# SCH_Two.net
KiCad netlist of a schematic drawn in Altium Designer
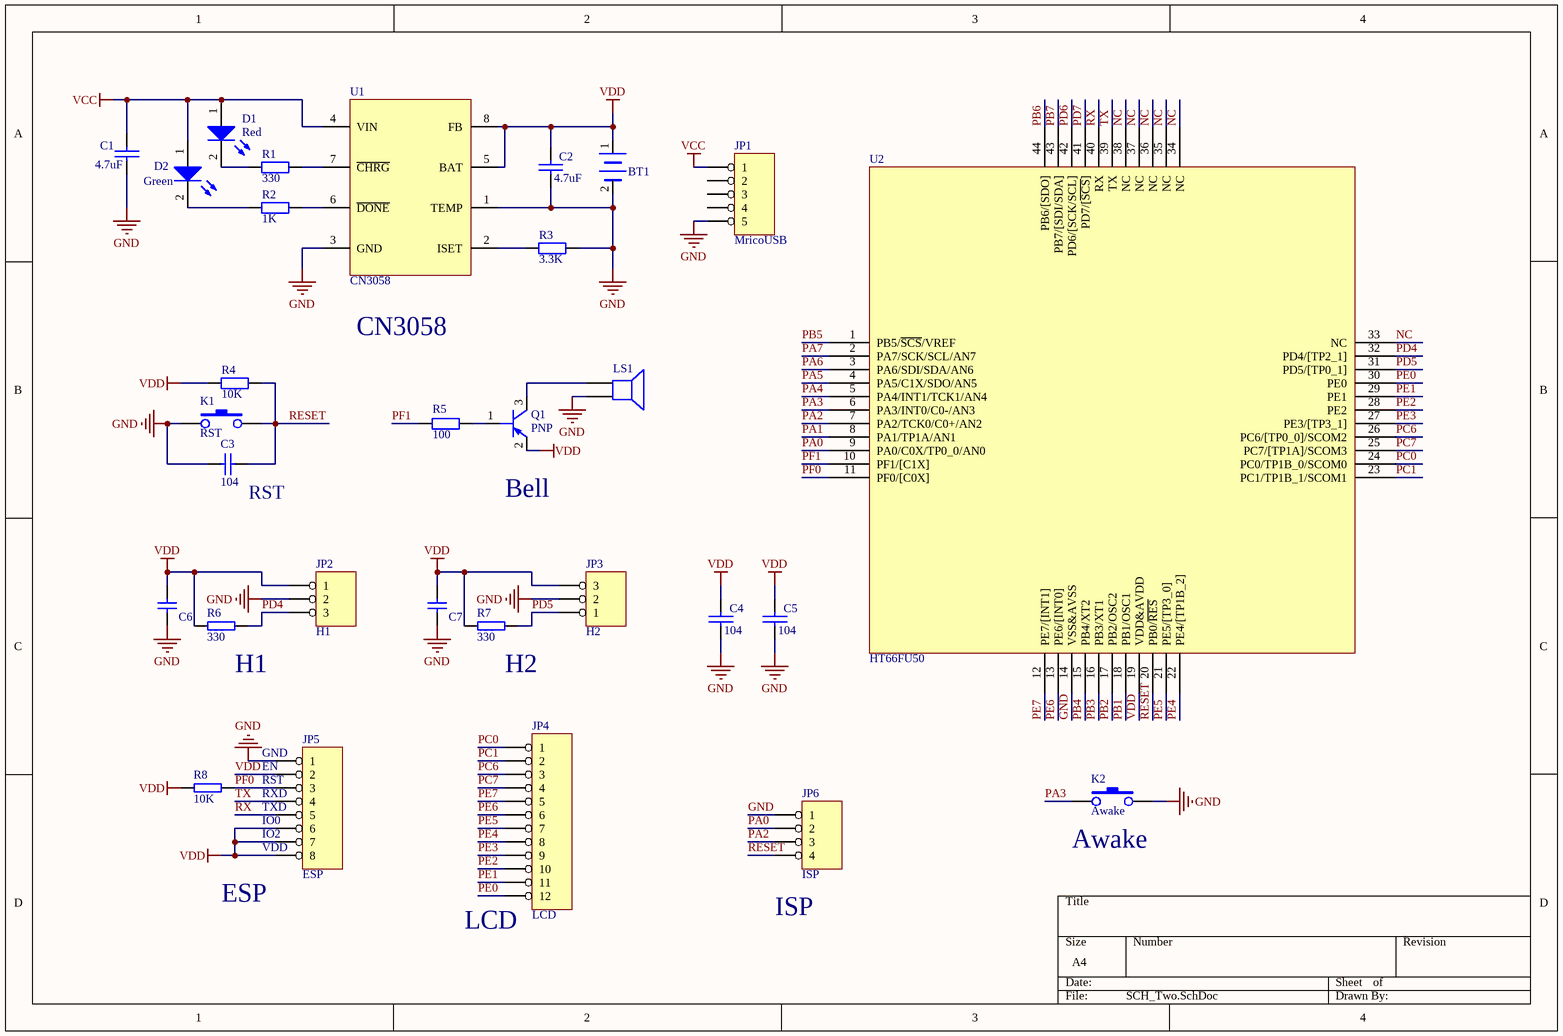
[diagram p0: SCH_Two.SchDoc]

(export (version "E")
  (design (tool "Eeschema 10.0.6"))
  (components
    (comp (ref "BT1")
      (value "BATTERY_1")
      (footprint "AAA Battery")
      (description "Battery")
      (libsource (lib "SkipThree") (part "BATTERY_1"))
    )
    (comp (ref "C1") (value "4.7uF") (footprint "0805") (libsource (lib "SkipCounter") (part "CAP1")))
    (comp (ref "C2") (value "4.7uF") (footprint "0805") (libsource (lib "SkipCounter") (part "CAP1")))
    (comp (ref "C3")
      (value "104")
      (footprint "0603")
      (description "无极性电容")
      (fields (field (name "Comment") "Cap") (field (name "PUBLISHER") "Altium Limited"))
      (libsource (lib "Library") (part "Cap"))
    )
    (comp (ref "C4") (value "104") (footprint "0603") (libsource (lib "SkipCounter") (part "CAP1")))
    (comp (ref "C5") (value "104") (footprint "0603") (libsource (lib "SkipCounter") (part "CAP1")))
    (comp (ref "C6")
      (value "CAP_1")
      (footprint "0603")
      (description "Capacitor")
      (libsource (lib "SCH") (part "CAP_1"))
    )
    (comp (ref "C7")
      (value "CAP_1")
      (footprint "0603")
      (description "Capacitor")
      (libsource (lib "SCH") (part "CAP_1"))
    )
    (comp (ref "D1")
      (value "Red")
      (footprint "0603")
      (description "LED灯")
      (libsource (lib "SkipThree") (part "LED"))
    )
    (comp (ref "D2")
      (value "Green")
      (footprint "0603")
      (description "LED灯")
      (libsource (lib "SkipThree") (part "LED"))
    )
    (comp (ref "JP1") (value "MricoUSB") (footprint "MircoUSB") (libsource (lib "SCH") (part "HEADER 5")))
    (comp (ref "JP2") (value "H1") (footprint "A3144") (libsource (lib "SCH") (part "HEADER 3")))
    (comp (ref "JP3") (value "H2") (footprint "A3144") (libsource (lib "") (part "HEADER 3_1")))
    (comp (ref "JP4") (value "LCD") (footprint "LCD1621") (libsource (lib "SCH") (part "HEADER 12")))
    (comp (ref "JP5") (value "ESP") (footprint "ESP8266-11") (libsource (lib "SCH") (part "HEADER 8")))
    (comp (ref "JP6") (value "ISP") (footprint "SIP4") (libsource (lib "SCH") (part "HEADER 4")))
    (comp (ref "K1")
      (value "RST")
      (footprint "KEY-SMT")
      (description "key")
      (libsource (lib "SCH") (part "SW-PB_1"))
    )
    (comp (ref "K2")
      (value "Awake")
      (footprint "KEY-SMT")
      (description "key")
      (libsource (lib "SCH") (part "SW-PB_1"))
    )
    (comp (ref "LS1") (value "SPEAKER") (footprint "Buzzer-Small") (libsource (lib "SCH") (part "SPEAKER")))
    (comp (ref "Q1")
      (value "PNP")
      (footprint "SOT-23")
      (description "PNP Transistor")
      (libsource (lib "SCH") (part "PNP"))
    )
    (comp (ref "R1")
      (value "330")
      (footprint "0603")
      (description "电阻")
      (libsource (lib "SkipThree") (part "Res2"))
    )
    (comp (ref "R2")
      (value "1K")
      (footprint "0603")
      (description "电阻")
      (libsource (lib "SkipThree") (part "Res2"))
    )
    (comp (ref "R3")
      (value "3.3K")
      (footprint "0603")
      (description "电阻")
      (libsource (lib "SkipThree") (part "Res2"))
    )
    (comp (ref "R4")
      (value "10K")
      (footprint "0603")
      (description "贴片电阻")
      (fields (field (name "Comment") "Res1") (field (name "PUBLISHER") "Altium Limited"))
      (libsource (lib "Library") (part "Res1"))
    )
    (comp (ref "R5")
      (value "100")
      (footprint "0603")
      (description "电阻")
      (libsource (lib "MyLibrary") (part "Res2"))
    )
    (comp (ref "R6")
      (value "330")
      (footprint "0603")
      (description "Resistor")
      (libsource (lib "SCH") (part "RES2"))
    )
    (comp (ref "R7")
      (value "330")
      (footprint "0603")
      (description "Resistor")
      (libsource (lib "SCH") (part "RES2"))
    )
    (comp (ref "R8")
      (value "10K")
      (footprint "0603")
      (description "Resistor")
      (libsource (lib "SCH") (part "RES2"))
    )
    (comp (ref "U1") (value "CN3058") (footprint "SO-8") (libsource (lib "SkipCounter") (part "CN3058")))
    (comp (ref "U2")
      (value "HT66FU50")
      (footprint "LQFP44")
      (fields (field (name "NAME") "HT66FU50"))
      (libsource (lib "HT66FU50") (part "HT66FU50"))
    )
  )
  (nets
    (net (code "1") (name "/NC") (class "Default")
      (node (ref "U2") (pin "33") (pinfunction "NC_33") (pintype "passive"))
      (node (ref "U2") (pin "34") (pinfunction "NC_34") (pintype "passive"))
      (node (ref "U2") (pin "35") (pinfunction "NC_35") (pintype "passive"))
      (node (ref "U2") (pin "36") (pinfunction "NC_36") (pintype "passive"))
      (node (ref "U2") (pin "37") (pinfunction "NC_37") (pintype "passive"))
      (node (ref "U2") (pin "38") (pinfunction "NC_38") (pintype "passive"))
    )
    (net (code "2") (name "/PA0") (class "Default")
      (node (ref "JP6") (pin "2") (pinfunction "2_2") (pintype "passive"))
      (node (ref "U2") (pin "9") (pinfunction "PA0/C0X/TP0_0/AN0_9") (pintype "passive"))
    )
    (net (code "3") (name "/PA1") (class "Default")
      (node (ref "U2") (pin "8") (pinfunction "PA1/TP1A/AN1_8") (pintype "passive"))
    )
    (net (code "4") (name "/PA2") (class "Default")
      (node (ref "JP6") (pin "3") (pinfunction "3_3") (pintype "passive"))
      (node (ref "U2") (pin "7") (pinfunction "PA2/TCK0/C0+/AN2_7") (pintype "passive"))
    )
    (net (code "5") (name "/PA3") (class "Default")
      (node (ref "K2") (pin "1") (pinfunction "1_1") (pintype "passive"))
      (node (ref "U2") (pin "6") (pinfunction "PA3/INT0/C0-/AN3_6") (pintype "passive"))
    )
    (net (code "6") (name "/PA4") (class "Default")
      (node (ref "U2") (pin "5") (pinfunction "PA4/INT1/TCK1/AN4_5") (pintype "passive"))
    )
    (net (code "7") (name "/PA5") (class "Default")
      (node (ref "U2") (pin "4") (pinfunction "PA5/C1X/SDO/AN5_4") (pintype "passive"))
    )
    (net (code "8") (name "/PA6") (class "Default")
      (node (ref "U2") (pin "3") (pinfunction "PA6/SDI/SDA/AN6_3") (pintype "passive"))
    )
    (net (code "9") (name "/PA7") (class "Default")
      (node (ref "U2") (pin "2") (pinfunction "PA7/SCK/SCL/AN7_2") (pintype "passive"))
    )
    (net (code "10") (name "/PB1") (class "Default")
      (node (ref "U2") (pin "18") (pinfunction "PB1/OSC1_18") (pintype "passive"))
    )
    (net (code "11") (name "/PB2") (class "Default")
      (node (ref "U2") (pin "17") (pinfunction "PB2/OSC2_17") (pintype "passive"))
    )
    (net (code "12") (name "/PB3") (class "Default")
      (node (ref "U2") (pin "16") (pinfunction "PB3/XT1_16") (pintype "passive"))
    )
    (net (code "13") (name "/PB4") (class "Default")
      (node (ref "U2") (pin "15") (pinfunction "PB4/XT2_15") (pintype "passive"))
    )
    (net (code "14") (name "/PB5") (class "Default")
      (node (ref "U2") (pin "1") (pinfunction "PB5/~{SCS}/VREF_1") (pintype "passive"))
    )
    (net (code "15") (name "/PB6") (class "Default")
      (node (ref "U2") (pin "44") (pinfunction "PB6/[SDO]_44") (pintype "passive"))
    )
    (net (code "16") (name "/PB7") (class "Default")
      (node (ref "U2") (pin "43") (pinfunction "PB7/[SDI/SDA]_43") (pintype "passive"))
    )
    (net (code "17") (name "/PC0") (class "Default")
      (node (ref "JP4") (pin "1") (pinfunction "1_1") (pintype "passive"))
      (node (ref "U2") (pin "24") (pinfunction "PC0/TP1B_0/SCOM0_24") (pintype "passive"))
    )
    (net (code "18") (name "/PC1") (class "Default")
      (node (ref "JP4") (pin "2") (pinfunction "2_2") (pintype "passive"))
      (node (ref "U2") (pin "23") (pinfunction "PC1/TP1B_1/SCOM1_23") (pintype "passive"))
    )
    (net (code "19") (name "/PC6") (class "Default")
      (node (ref "JP4") (pin "3") (pinfunction "3_3") (pintype "passive"))
      (node (ref "U2") (pin "26") (pinfunction "PC6/[TP0_0]/SCOM2_26") (pintype "passive"))
    )
    (net (code "20") (name "/PC7") (class "Default")
      (node (ref "JP4") (pin "4") (pinfunction "4_4") (pintype "passive"))
      (node (ref "U2") (pin "25") (pinfunction "PC7/[TP1A]/SCOM3_25") (pintype "passive"))
    )
    (net (code "21") (name "/PD4") (class "Default")
      (node (ref "JP2") (pin "3") (pinfunction "3_3") (pintype "passive"))
      (node (ref "R6") (pin "2") (pinfunction "2_2") (pintype "passive"))
      (node (ref "U2") (pin "32") (pinfunction "PD4/[TP2_1]_32") (pintype "passive"))
    )
    (net (code "22") (name "/PD5") (class "Default")
      (node (ref "JP3") (pin "1") (pinfunction "1_1") (pintype "passive"))
      (node (ref "R7") (pin "2") (pinfunction "2_2") (pintype "passive"))
      (node (ref "U2") (pin "31") (pinfunction "PD5/[TP0_1]_31") (pintype "passive"))
    )
    (net (code "23") (name "/PD6") (class "Default")
      (node (ref "U2") (pin "42") (pinfunction "PD6/[SCK/SCL]_42") (pintype "passive"))
    )
    (net (code "24") (name "/PD7") (class "Default")
      (node (ref "U2") (pin "41") (pinfunction "PD7/[~{SCS}]_41") (pintype "passive"))
    )
    (net (code "25") (name "/PE0") (class "Default")
      (node (ref "JP4") (pin "12") (pinfunction "12_12") (pintype "passive"))
      (node (ref "U2") (pin "30") (pinfunction "PE0_30") (pintype "passive"))
    )
    (net (code "26") (name "/PE1") (class "Default")
      (node (ref "JP4") (pin "11") (pinfunction "11_11") (pintype "passive"))
      (node (ref "U2") (pin "29") (pinfunction "PE1_29") (pintype "passive"))
    )
    (net (code "27") (name "/PE2") (class "Default")
      (node (ref "JP4") (pin "10") (pinfunction "10_10") (pintype "passive"))
      (node (ref "U2") (pin "28") (pinfunction "PE2_28") (pintype "passive"))
    )
    (net (code "28") (name "/PE3") (class "Default")
      (node (ref "JP4") (pin "9") (pinfunction "9_9") (pintype "passive"))
      (node (ref "U2") (pin "27") (pinfunction "PE3/[TP3_1]_27") (pintype "passive"))
    )
    (net (code "29") (name "/PE4") (class "Default")
      (node (ref "JP4") (pin "8") (pinfunction "8_8") (pintype "passive"))
      (node (ref "U2") (pin "22") (pinfunction "PE4/[TP1B_2]_22") (pintype "passive"))
    )
    (net (code "30") (name "/PE5") (class "Default")
      (node (ref "JP4") (pin "7") (pinfunction "7_7") (pintype "passive"))
      (node (ref "U2") (pin "21") (pinfunction "PE5/[TP3_0]_21") (pintype "passive"))
    )
    (net (code "31") (name "/PE6") (class "Default")
      (node (ref "JP4") (pin "6") (pinfunction "6_6") (pintype "passive"))
      (node (ref "U2") (pin "13") (pinfunction "PE6/[INT0]_13") (pintype "passive"))
    )
    (net (code "32") (name "/PE7") (class "Default")
      (node (ref "JP4") (pin "5") (pinfunction "5_5") (pintype "passive"))
      (node (ref "U2") (pin "12") (pinfunction "PE7/[INT1]_12") (pintype "passive"))
    )
    (net (code "33") (name "/PF0") (class "Default")
      (node (ref "JP5") (pin "3") (pinfunction "3_3") (pintype "passive"))
      (node (ref "R8") (pin "2") (pinfunction "2_2") (pintype "passive"))
      (node (ref "U2") (pin "11") (pinfunction "PF0/[C0X]_11") (pintype "passive"))
    )
    (net (code "34") (name "/PF1") (class "Default")
      (node (ref "R5") (pin "2") (pinfunction "2_2") (pintype "passive"))
      (node (ref "U2") (pin "10") (pinfunction "PF1/[C1X]_10") (pintype "passive"))
    )
    (net (code "35") (name "/RESET") (class "Default")
      (node (ref "C3") (pin "2") (pinfunction "2_2") (pintype "passive"))
      (node (ref "JP6") (pin "4") (pinfunction "4_4") (pintype "passive"))
      (node (ref "K1") (pin "2") (pinfunction "2_2") (pintype "passive"))
      (node (ref "R4") (pin "2") (pinfunction "2_2") (pintype "passive"))
      (node (ref "U2") (pin "20") (pinfunction "PB0/~{RES}_20") (pintype "passive"))
    )
    (net (code "36") (name "/RX") (class "Default")
      (node (ref "JP5") (pin "5") (pinfunction "5_5") (pintype "passive"))
      (node (ref "U2") (pin "40") (pinfunction "RX_40") (pintype "passive"))
    )
    (net (code "37") (name "/TX") (class "Default")
      (node (ref "JP5") (pin "4") (pinfunction "4_4") (pintype "passive"))
      (node (ref "U2") (pin "39") (pinfunction "TX_39") (pintype "passive"))
    )
    (net (code "38") (name "GND") (class "Default")
      (node (ref "BT1") (pin "2") (pinfunction "-_2") (pintype "passive"))
      (node (ref "C1") (pin "1") (pinfunction "1_1") (pintype "passive"))
      (node (ref "C2") (pin "1") (pinfunction "1_1") (pintype "passive"))
      (node (ref "C3") (pin "1") (pinfunction "1_1") (pintype "passive"))
      (node (ref "C4") (pin "1") (pinfunction "1_1") (pintype "passive"))
      (node (ref "C5") (pin "1") (pinfunction "1_1") (pintype "passive"))
      (node (ref "C6") (pin "1") (pinfunction "1_1") (pintype "passive"))
      (node (ref "C7") (pin "1") (pinfunction "1_1") (pintype "passive"))
      (node (ref "JP1") (pin "5") (pinfunction "5_5") (pintype "passive"))
      (node (ref "JP2") (pin "2") (pinfunction "2_2") (pintype "passive"))
      (node (ref "JP3") (pin "2") (pinfunction "2_2") (pintype "passive"))
      (node (ref "JP5") (pin "1") (pinfunction "1_1") (pintype "passive"))
      (node (ref "JP6") (pin "1") (pinfunction "1_1") (pintype "passive"))
      (node (ref "K1") (pin "1") (pinfunction "1_1") (pintype "passive"))
      (node (ref "K2") (pin "2") (pinfunction "2_2") (pintype "passive"))
      (node (ref "LS1") (pin "2") (pinfunction "2_2") (pintype "passive"))
      (node (ref "R3") (pin "2") (pinfunction "2_2") (pintype "passive"))
      (node (ref "U1") (pin "1") (pinfunction "TEMP_1") (pintype "passive"))
      (node (ref "U1") (pin "3") (pinfunction "GND_3") (pintype "passive"))
      (node (ref "U2") (pin "14") (pinfunction "VSS&AVSS_14") (pintype "passive"))
    )
    (net (code "39") (name "Net-(D1-K)") (class "Default")
      (node (ref "D1") (pin "2") (pinfunction "K_2") (pintype "passive"))
      (node (ref "R1") (pin "1") (pinfunction "1_1") (pintype "passive"))
    )
    (net (code "40") (name "Net-(D2-K)") (class "Default")
      (node (ref "D2") (pin "2") (pinfunction "K_2") (pintype "passive"))
      (node (ref "R2") (pin "1") (pinfunction "1_1") (pintype "passive"))
    )
    (net (code "41") (name "Net-(Q1-BASE)") (class "Default")
      (node (ref "Q1") (pin "1") (pinfunction "BASE_1") (pintype "open_collector"))
      (node (ref "R5") (pin "1") (pinfunction "1_1") (pintype "passive"))
    )
    (net (code "42") (name "Net-(Q1-COLLECTOR)") (class "Default")
      (node (ref "LS1") (pin "1") (pinfunction "1_1") (pintype "passive"))
      (node (ref "Q1") (pin "3") (pinfunction "COLLECTOR_3") (pintype "open_collector"))
    )
    (net (code "43") (name "Net-(U1-ISET)") (class "Default")
      (node (ref "R3") (pin "1") (pinfunction "1_1") (pintype "passive"))
      (node (ref "U1") (pin "2") (pinfunction "ISET_2") (pintype "passive"))
    )
    (net (code "44") (name "Net-(U1-~{CHRG})") (class "Default")
      (node (ref "R1") (pin "2") (pinfunction "2_2") (pintype "passive"))
      (node (ref "U1") (pin "7") (pinfunction "~{CHRG}_7") (pintype "passive"))
    )
    (net (code "45") (name "Net-(U1-~{DONE})") (class "Default")
      (node (ref "R2") (pin "2") (pinfunction "2_2") (pintype "passive"))
      (node (ref "U1") (pin "6") (pinfunction "~{DONE}_6") (pintype "passive"))
    )
    (net (code "46") (name "VCC") (class "Default")
      (node (ref "C1") (pin "2") (pinfunction "2_2") (pintype "passive"))
      (node (ref "D1") (pin "1") (pinfunction "A_1") (pintype "passive"))
      (node (ref "D2") (pin "1") (pinfunction "A_1") (pintype "passive"))
      (node (ref "JP1") (pin "1") (pinfunction "1_1") (pintype "passive"))
      (node (ref "U1") (pin "4") (pinfunction "VIN_4") (pintype "passive"))
    )
    (net (code "47") (name "VDD") (class "Default")
      (node (ref "BT1") (pin "1") (pinfunction "+_1") (pintype "passive"))
      (node (ref "C2") (pin "2") (pinfunction "2_2") (pintype "passive"))
      (node (ref "C4") (pin "2") (pinfunction "2_2") (pintype "passive"))
      (node (ref "C5") (pin "2") (pinfunction "2_2") (pintype "passive"))
      (node (ref "C6") (pin "2") (pinfunction "2_2") (pintype "passive"))
      (node (ref "C7") (pin "2") (pinfunction "2_2") (pintype "passive"))
      (node (ref "JP2") (pin "1") (pinfunction "1_1") (pintype "passive"))
      (node (ref "JP3") (pin "3") (pinfunction "3_3") (pintype "passive"))
      (node (ref "JP5") (pin "2") (pinfunction "2_2") (pintype "passive"))
      (node (ref "JP5") (pin "6") (pinfunction "6_6") (pintype "passive"))
      (node (ref "JP5") (pin "7") (pinfunction "7_7") (pintype "passive"))
      (node (ref "JP5") (pin "8") (pinfunction "8_8") (pintype "passive"))
      (node (ref "Q1") (pin "2") (pinfunction "EMITTER_2") (pintype "open_emitter"))
      (node (ref "R4") (pin "1") (pinfunction "1_1") (pintype "passive"))
      (node (ref "R6") (pin "1") (pinfunction "1_1") (pintype "passive"))
      (node (ref "R7") (pin "1") (pinfunction "1_1") (pintype "passive"))
      (node (ref "R8") (pin "1") (pinfunction "1_1") (pintype "passive"))
      (node (ref "U1") (pin "5") (pinfunction "BAT_5") (pintype "passive"))
      (node (ref "U1") (pin "8") (pinfunction "FB_8") (pintype "passive"))
      (node (ref "U2") (pin "19") (pinfunction "VDD&AVDD_19") (pintype "passive"))
    )
    (net (code "48") (name "unconnected-(JP1-Pad2)") (class "Default")
      (node (ref "JP1") (pin "2") (pinfunction "2_2") (pintype "passive"))
    )
    (net (code "49") (name "unconnected-(JP1-Pad3)") (class "Default")
      (node (ref "JP1") (pin "3") (pinfunction "3_3") (pintype "passive"))
    )
    (net (code "50") (name "unconnected-(JP1-Pad4)") (class "Default")
      (node (ref "JP1") (pin "4") (pinfunction "4_4") (pintype "passive"))
    )
  )
)
